# Connections.net
KiCad netlist of a schematic drawn in Altium Designer
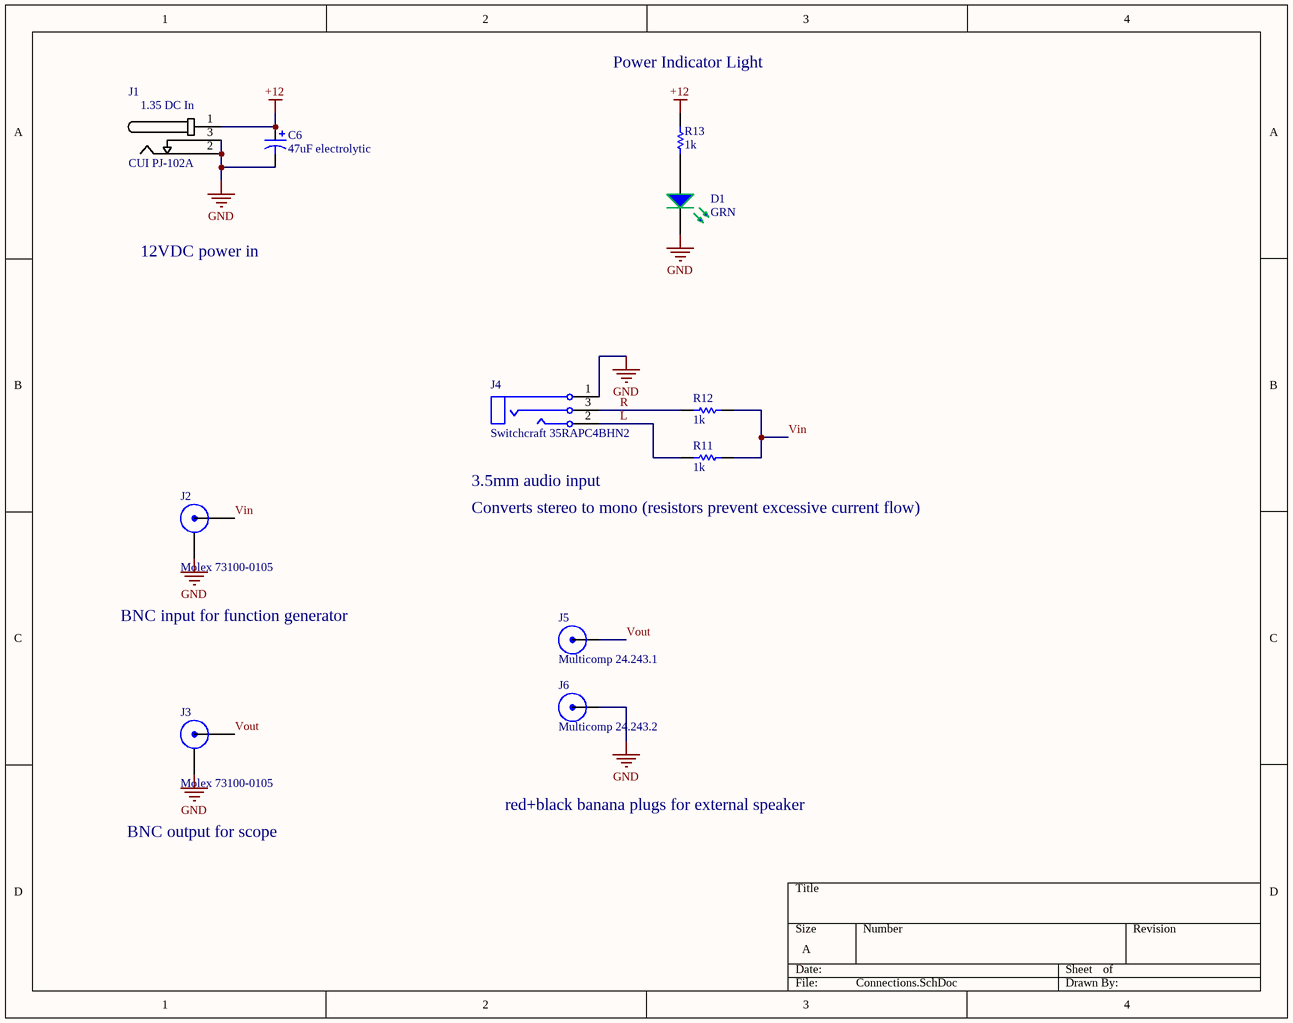
[diagram p0: Connections.SchDoc]

(export (version "E")
  (design (tool "Eeschema 10.0.6"))
  (components
    (comp (ref "C6")
      (value "47uF electrolytic")
      (footprint "PCB-bs2nfpedd8vjo8odb39w-1")
      (description "Cap Aluminum Lytic 47uF 50V 20% (6.3 X 11.2mm) Radial 2.5mm 260mA 1000h 105C Automotive Bulk")
      (fields (field (name "MANUFACTURER PART NUMBER") "EEU-FC1H470"))
      (libsource (lib "Octopart library") (part "SYM-6ed4a5842ea2b113-1"))
    )
    (comp (ref "D1")
      (value "GRN")
      (footprint "PCBComponent_1")
      (description "5mm Lens, One Position CBI ; Emitting Color Green with Green Diffused Lens")
      (fields (field (name "MANUFACTURER PART NUMBER") "XVB1LUG50D"))
      (libsource (lib "Octopart library") (part "SYM-402b88aa3a7d9fec-1"))
    )
    (comp (ref "J1")
      (value "CUI PJ-102A")
      (footprint "PCBComponent_1 - duplicate")
      (description "FolioGadgets DC Jack")
      (fields (field (name "MANUFACTURER PART NUMBER") "B06XQ2JGQQ"))
      (libsource (lib "Octopart library") (part "SYM-2700effd37adf8c7-1"))
    )
    (comp (ref "J2")
      (value "Molex 73100-0105")
      (footprint "PCB-581953-1")
      (description "50 Ohms, BNC Right-Angle PCB Jack Receptacle, Nickel Plated Zinc Alloy Body, Low Profile")
      (fields (field (name "MANUFACTURER PART NUMBER") "73100-0105"))
      (libsource (lib "Octopart library") (part "SYM-581953-1"))
    )
    (comp (ref "J3")
      (value "Molex 73100-0105")
      (footprint "PCB-581953-1")
      (description "50 Ohms, BNC Right-Angle PCB Jack Receptacle, Nickel Plated Zinc Alloy Body, Low Profile")
      (fields (field (name "MANUFACTURER PART NUMBER") "73100-0105"))
      (libsource (lib "Octopart library") (part "SYM-581953-1"))
    )
    (comp (ref "J4")
      (value "Switchcraft 35RAPC4BHN2")
      (footprint "PCB-329508-1")
      (description "CONN JACK STEREO 3.5MM HORIZON")
      (fields (field (name "MANUFACTURER PART NUMBER") "35RAPC4BHN2"))
      (libsource (lib "Octopart library") (part "SYM-329508-1"))
    )
    (comp (ref "J5")
      (value "Multicomp 24.243.1")
      (footprint "PCB-1keg917tfggg2k36z9zw-1")
      (description "Banana Test Connector, 4mm, Jack, PCB Mount, 20 A, 30 V, Silver Plated Contacts, Red")
      (fields (field (name "MANUFACTURER PART NUMBER") "24.243.1"))
      (libsource (lib "Octopart library") (part "SYM-20399854-1"))
    )
    (comp (ref "J6")
      (value "Multicomp 24.243.2")
      (footprint "PCB-20399855-1")
      (description "Banana Test Connector, 4mm, Jack, PCB Mount, 20 A, 30 V, Silver Plated Contacts, Black")
      (fields (field (name "MANUFACTURER PART NUMBER") "24.243.2"))
      (libsource (lib "Octopart library") (part "SYM-20399855-1"))
    )
    (comp (ref "R11")
      (value "1k")
      (footprint "PCB-ufx52wqpb97u1085hkka-1")
      (description "Through Hole Carbon Film Resistor, CFR Series, 10 kohm, 500 mW, - 5%, 350 V, Axial Leaded")
      (libsource (lib "Octopart library") (part "SYM-0abbc281a318d57c-1"))
    )
    (comp (ref "R12")
      (value "1k")
      (footprint "PCB-ufx52wqpb97u1085hkka-1")
      (description "Through Hole Carbon Film Resistor, CFR Series, 10 kohm, 500 mW, - 5%, 350 V, Axial Leaded")
      (libsource (lib "Octopart library") (part "SYM-0abbc281a318d57c-1"))
    )
    (comp (ref "R13")
      (value "1k")
      (footprint "PCB-ufx52wqpb97u1085hkka-1")
      (description "Through Hole Carbon Film Resistor, CFR Series, 10 kohm, 500 mW, - 5%, 350 V, Axial Leaded")
      (libsource (lib "Octopart library") (part "SYM-0abbc281a318d57c-1"))
    )
  )
  (nets
    (net (code "1") (name "+12") (class "Default")
      (node (ref "C6") (pin "1") (pinfunction "1_1") (pintype "passive"))
      (node (ref "J1") (pin "1") (pinfunction "1_1") (pintype "power_in"))
      (node (ref "R13") (pin "2") (pinfunction "2_2") (pintype "passive"))
    )
    (net (code "2") (name "/L") (class "Default")
      (node (ref "J4") (pin "2") (pinfunction "TIP_2") (pintype "passive"))
      (node (ref "R11") (pin "2") (pinfunction "2_2") (pintype "passive"))
    )
    (net (code "3") (name "/R") (class "Default")
      (node (ref "J4") (pin "3") (pinfunction "RING_3") (pintype "passive"))
      (node (ref "R12") (pin "2") (pinfunction "2_2") (pintype "passive"))
    )
    (net (code "4") (name "/Vin") (class "Default")
      (node (ref "J2") (pin "1") (pinfunction "1_1") (pintype "passive"))
      (node (ref "R11") (pin "1") (pinfunction "1_1") (pintype "passive"))
      (node (ref "R12") (pin "1") (pinfunction "1_1") (pintype "passive"))
    )
    (net (code "5") (name "/Vout") (class "Default")
      (node (ref "J3") (pin "1") (pinfunction "1_1") (pintype "passive"))
      (node (ref "J5") (pin "1") (pinfunction "1_1") (pintype "passive"))
    )
    (net (code "6") (name "GND") (class "Default")
      (node (ref "C6") (pin "2") (pinfunction "2_2") (pintype "passive"))
      (node (ref "D1") (pin "2") (pinfunction "K_2") (pintype "passive"))
      (node (ref "J1") (pin "2") (pinfunction "2_2") (pintype "passive"))
      (node (ref "J1") (pin "3") (pinfunction "3_3") (pintype "passive"))
      (node (ref "J2") (pin "2") (pinfunction "2_2") (pintype "passive"))
      (node (ref "J3") (pin "2") (pinfunction "2_2") (pintype "passive"))
      (node (ref "J4") (pin "1") (pinfunction "SLEEVE_1") (pintype "passive"))
      (node (ref "J6") (pin "1") (pinfunction "1_1") (pintype "passive"))
    )
    (net (code "7") (name "Net-(D1-A)") (class "Default")
      (node (ref "D1") (pin "1") (pinfunction "A_1") (pintype "passive"))
      (node (ref "R13") (pin "1") (pinfunction "1_1") (pintype "passive"))
    )
  )
)
